# digiadb.net
KiCad netlist of a schematic drawn in EAGLE
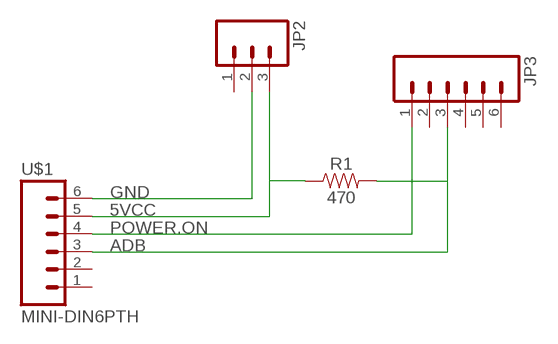
[diagram p0: schematic, sheet 1]

(export (version "E")
  (design (tool "Eeschema 10.0.6"))
  (components
    (comp (ref "JP2")
      (value "M03PTH")
      (footprint "eagle-import:1X03")
      (libsource (lib "eagle-import") (part "M03PTH"))
    )
    (comp (ref "JP3")
      (value "M06SIP")
      (footprint "eagle-import:1X06")
      (libsource (lib "eagle-import") (part "M06SIP"))
    )
    (comp (ref "R1")
      (value "470")
      (footprint "eagle-import:0603")
      (libsource (lib "eagle-import") (part "470OHM-0603-1/10W-1%"))
    )
    (comp (ref "U$1")
      (value "MINI-DIN6PTH")
      (footprint "eagle-import:MINI-DIN6")
      (libsource (lib "eagle-import") (part "MINI-DIN6PTH"))
    )
  )
  (nets
    (net (code "1") (name "/5VCC") (class "Default")
      (node (ref "JP2") (pin "3") (pinfunction "3_3") (pintype "passive"))
      (node (ref "R1") (pin "1") (pinfunction "1_1") (pintype "passive"))
      (node (ref "U$1") (pin "5") (pinfunction "5_5") (pintype "passive"))
    )
    (net (code "2") (name "/ADB") (class "Default")
      (node (ref "JP3") (pin "3") (pinfunction "3_3") (pintype "passive"))
      (node (ref "R1") (pin "2") (pinfunction "2_2") (pintype "passive"))
      (node (ref "U$1") (pin "3") (pinfunction "3_3") (pintype "passive"))
    )
    (net (code "3") (name "/GND") (class "Default")
      (node (ref "JP2") (pin "2") (pinfunction "2_2") (pintype "passive"))
      (node (ref "U$1") (pin "6") (pinfunction "6_6") (pintype "passive"))
    )
    (net (code "4") (name "/POWER.ON") (class "Default")
      (node (ref "JP3") (pin "1") (pinfunction "1_1") (pintype "passive"))
      (node (ref "U$1") (pin "4") (pinfunction "4_4") (pintype "passive"))
    )
    (net (code "5") (name "unconnected-(JP2-Pad1)") (class "Default")
      (node (ref "JP2") (pin "1") (pinfunction "1_1") (pintype "passive"))
    )
    (net (code "6") (name "unconnected-(JP3-Pad2)") (class "Default")
      (node (ref "JP3") (pin "2") (pinfunction "2_2") (pintype "passive"))
    )
    (net (code "7") (name "unconnected-(JP3-Pad4)") (class "Default")
      (node (ref "JP3") (pin "4") (pinfunction "4_4") (pintype "passive"))
    )
    (net (code "8") (name "unconnected-(JP3-Pad5)") (class "Default")
      (node (ref "JP3") (pin "5") (pinfunction "5_5") (pintype "passive"))
    )
    (net (code "9") (name "unconnected-(JP3-Pad6)") (class "Default")
      (node (ref "JP3") (pin "6") (pinfunction "6_6") (pintype "passive"))
    )
    (net (code "10") (name "unconnected-(U$1-Pad1)") (class "Default")
      (node (ref "U$1") (pin "1") (pinfunction "1_1") (pintype "passive"))
    )
    (net (code "11") (name "unconnected-(U$1-Pad2)") (class "Default")
      (node (ref "U$1") (pin "2") (pinfunction "2_2") (pintype "passive"))
    )
  )
)
